# SR_Latch.net
KiCad netlist of a schematic drawn in Altium Designer
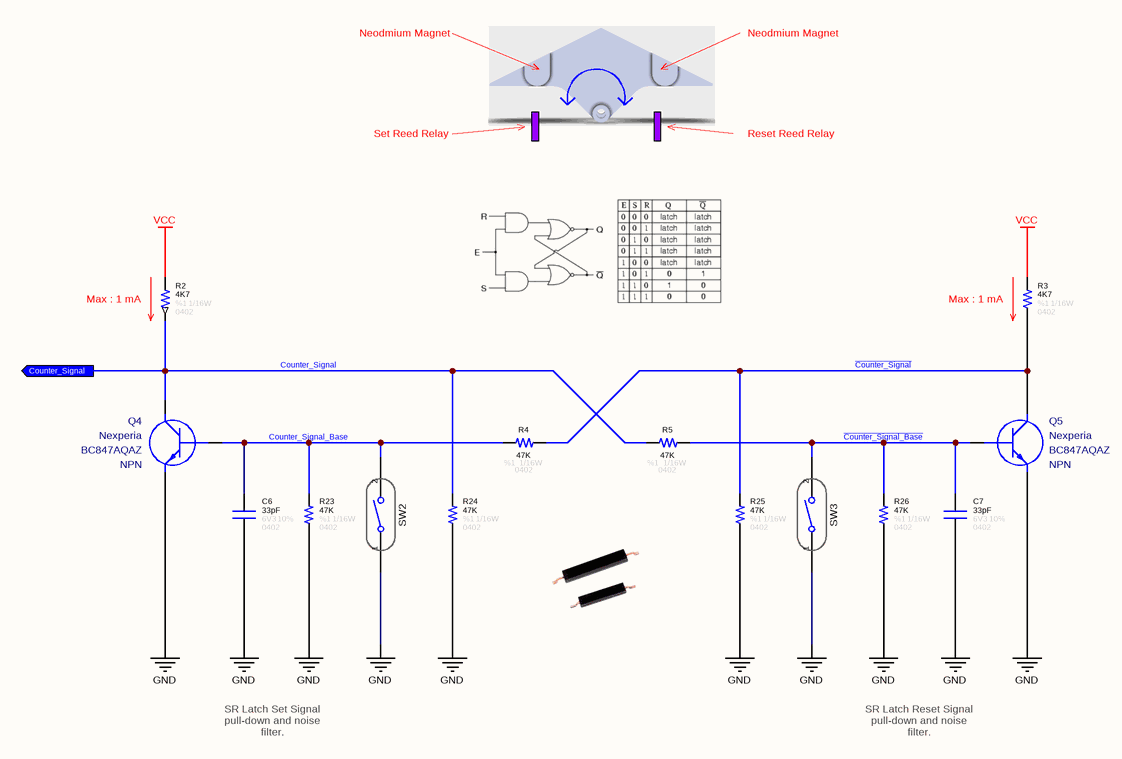
[diagram p0: SR Latch.SchDoc]

(export (version "E")
  (design (tool "Eeschema 10.0.6"))
  (components
    (comp (ref "C6")
      (value "33pF")
      (footprint "CAPACITOR_0402")
      (description "Capacitor - 33pF [0402] (Ceramic)")
      (fields
        (field (name "MANUFACTURER PART NUMBER") "C0402C330J9RACAUTO")
        (field (name "TOLERANCE") "10%")
        (field (name "CASE") "0402")
        (field (name "VOLTAGE") "6V3")
      )
      (libsource (lib "P101DA_Library") (part "Capacitor - 33pF [0402-6V3]"))
    )
    (comp (ref "C7")
      (value "33pF")
      (footprint "CAPACITOR_0402")
      (description "Capacitor - 33pF [0402] (Ceramic)")
      (fields
        (field (name "MANUFACTURER PART NUMBER") "C0402C330J9RACAUTO")
        (field (name "TOLERANCE") "10%")
        (field (name "CASE") "0402")
        (field (name "VOLTAGE") "6V3")
      )
      (libsource (lib "P101DA_Library") (part "Capacitor - 33pF [0402-6V3]"))
    )
    (comp (ref "Q4")
      (value "BC847AQAZ")
      (footprint "SOT1215")
      (description "Bipolar NPN Transistors")
      (fields
        (field (name "MANUFACTURER NAME") "Nexperia")
        (field (name "MANUFACTURER PART NUMBER") "BC847AQAZ")
        (field (name "POLARITY") "NPN")
      )
      (libsource (lib "P101DA_Library") (part "Transistor - BC847"))
    )
    (comp (ref "Q5")
      (value "BC847AQAZ")
      (footprint "SOT1215")
      (description "Bipolar NPN Transistors")
      (fields
        (field (name "MANUFACTURER NAME") "Nexperia")
        (field (name "MANUFACTURER PART NUMBER") "BC847AQAZ")
        (field (name "POLARITY") "NPN")
      )
      (libsource (lib "P101DA_Library") (part "Transistor - BC847"))
    )
    (comp (ref "R2")
      (value "4K7")
      (footprint "RESISTOR_0402")
      (description "Thick Film Resistors - SMD 1/16 W 4.7 KOhm 1%")
      (fields
        (field (name "MANUFACTURER PART NUMBER") "CRCW04024K70FKED")
        (field (name "TOLERANCE") "%1")
        (field (name "CASE") "0402")
        (field (name "POWER") "1/16W")
        (field (name "Comment") "4K7 - 0402 - %1 - 1/16W")
      )
      (libsource (lib "P101DA_Library") (part "Resistor - 4K7 [0402]"))
    )
    (comp (ref "R3")
      (value "4K7")
      (footprint "RESISTOR_0402")
      (description "Thick Film Resistors - SMD 1/16 W 4.7 KOhm 1%")
      (fields
        (field (name "MANUFACTURER PART NUMBER") "CRCW04024K70FKED")
        (field (name "TOLERANCE") "%1")
        (field (name "CASE") "0402")
        (field (name "POWER") "1/16W")
        (field (name "Comment") "4K7 - 0402 - %1 - 1/16W")
      )
      (libsource (lib "P101DA_Library") (part "Resistor - 4K7 [0402]"))
    )
    (comp (ref "R4")
      (value "47K")
      (footprint "RESISTOR_0402")
      (description "Thick Film Resistors - SMD 1/16 W 47 KOhm 1%")
      (fields
        (field (name "MANUFACTURER PART NUMBER") "CRCW040247K0FKED")
        (field (name "TOLERANCE") "%1")
        (field (name "CASE") "0402")
        (field (name "POWER") "1/16W")
        (field (name "Comment") "47K - 0402 - %1 - 1/16W")
      )
      (libsource (lib "P101DA_Library") (part "Resistor - 47K [0402]"))
    )
    (comp (ref "R5")
      (value "47K")
      (footprint "RESISTOR_0402")
      (description "Thick Film Resistors - SMD 1/16 W 47 KOhm 1%")
      (fields
        (field (name "MANUFACTURER PART NUMBER") "CRCW040247K0FKED")
        (field (name "TOLERANCE") "%1")
        (field (name "CASE") "0402")
        (field (name "POWER") "1/16W")
        (field (name "Comment") "47K - 0402 - %1 - 1/16W")
      )
      (libsource (lib "P101DA_Library") (part "Resistor - 47K [0402]"))
    )
    (comp (ref "R23")
      (value "47K")
      (footprint "RESISTOR_0402")
      (description "Thick Film Resistors - SMD 1/16 W 47 KOhm 1%")
      (fields
        (field (name "MANUFACTURER PART NUMBER") "CRCW040247K0FKED")
        (field (name "TOLERANCE") "%1")
        (field (name "CASE") "0402")
        (field (name "POWER") "1/16W")
        (field (name "Comment") "47K - 0402 - %1 - 1/16W")
      )
      (libsource (lib "P101DA_Library") (part "Resistor - 47K [0402]"))
    )
    (comp (ref "R24")
      (value "47K")
      (footprint "RESISTOR_0402")
      (description "Thick Film Resistors - SMD 1/16 W 47 KOhm 1%")
      (fields
        (field (name "MANUFACTURER PART NUMBER") "CRCW040247K0FKED")
        (field (name "TOLERANCE") "%1")
        (field (name "CASE") "0402")
        (field (name "POWER") "1/16W")
        (field (name "Comment") "47K - 0402 - %1 - 1/16W")
      )
      (libsource (lib "P101DA_Library") (part "Resistor - 47K [0402]"))
    )
    (comp (ref "R25")
      (value "47K")
      (footprint "RESISTOR_0402")
      (description "Thick Film Resistors - SMD 1/16 W 47 KOhm 1%")
      (fields
        (field (name "MANUFACTURER PART NUMBER") "CRCW040247K0FKED")
        (field (name "TOLERANCE") "%1")
        (field (name "CASE") "0402")
        (field (name "POWER") "1/16W")
        (field (name "Comment") "47K - 0402 - %1 - 1/16W")
      )
      (libsource (lib "P101DA_Library") (part "Resistor - 47K [0402]"))
    )
    (comp (ref "R26")
      (value "47K")
      (footprint "RESISTOR_0402")
      (description "Thick Film Resistors - SMD 1/16 W 47 KOhm 1%")
      (fields
        (field (name "MANUFACTURER PART NUMBER") "CRCW040247K0FKED")
        (field (name "TOLERANCE") "%1")
        (field (name "CASE") "0402")
        (field (name "POWER") "1/16W")
        (field (name "Comment") "47K - 0402 - %1 - 1/16W")
      )
      (libsource (lib "P101DA_Library") (part "Resistor - 47K [0402]"))
    )
    (comp (ref "SW2")
      (value "Reed Relay")
      (footprint "REED Relay")
      (description "Reed relay - SMD 11.7 mm")
      (fields (field (name "MANUFACTURER PART NUMBER") "MKA-10110MS"))
      (libsource (lib "P101DA_Library") (part "Switch - Reed Relay"))
    )
    (comp (ref "SW3")
      (value "Reed Relay")
      (footprint "REED Relay")
      (description "Reed relay - SMD 11.7 mm")
      (fields (field (name "MANUFACTURER PART NUMBER") "MKA-10110MS"))
      (libsource (lib "P101DA_Library") (part "Switch - Reed Relay"))
    )
  )
  (nets
    (net (code "1") (name "/Counter_Signal") (class "Default")
      (node (ref "Q4") (pin "3") (pinfunction "C_3") (pintype "passive"))
      (node (ref "R2") (pin "1") (pinfunction "1_1") (pintype "output"))
      (node (ref "R24") (pin "2") (pinfunction "2_2") (pintype "passive"))
      (node (ref "R5") (pin "2") (pinfunction "2_2") (pintype "passive"))
    )
    (net (code "2") (name "/Counter_Signal_Base") (class "Default")
      (node (ref "C6") (pin "2") (pinfunction "2_2") (pintype "passive"))
      (node (ref "Q4") (pin "1") (pinfunction "B_1") (pintype "passive"))
      (node (ref "R23") (pin "2") (pinfunction "2_2") (pintype "passive"))
      (node (ref "R4") (pin "2") (pinfunction "2_2") (pintype "passive"))
      (node (ref "SW2") (pin "2") (pinfunction "COM_2") (pintype "passive"))
    )
    (net (code "3") (name "/~{Counter_Signal_Base}") (class "Default")
      (node (ref "C7") (pin "2") (pinfunction "2_2") (pintype "passive"))
      (node (ref "Q5") (pin "1") (pinfunction "B_1") (pintype "passive"))
      (node (ref "R26") (pin "2") (pinfunction "2_2") (pintype "passive"))
      (node (ref "R5") (pin "1") (pinfunction "1_1") (pintype "passive"))
      (node (ref "SW3") (pin "2") (pinfunction "COM_2") (pintype "passive"))
    )
    (net (code "4") (name "/~{Counter_Signal}") (class "Default")
      (node (ref "Q5") (pin "3") (pinfunction "C_3") (pintype "passive"))
      (node (ref "R25") (pin "2") (pinfunction "2_2") (pintype "passive"))
      (node (ref "R3") (pin "1") (pinfunction "1_1") (pintype "output"))
      (node (ref "R4") (pin "1") (pinfunction "1_1") (pintype "passive"))
    )
    (net (code "5") (name "GND") (class "Default")
      (node (ref "C6") (pin "1") (pinfunction "1_1") (pintype "passive"))
      (node (ref "C7") (pin "1") (pinfunction "1_1") (pintype "passive"))
      (node (ref "Q4") (pin "2") (pinfunction "E_2") (pintype "passive"))
      (node (ref "Q5") (pin "2") (pinfunction "E_2") (pintype "passive"))
      (node (ref "R23") (pin "1") (pinfunction "1_1") (pintype "passive"))
      (node (ref "R24") (pin "1") (pinfunction "1_1") (pintype "passive"))
      (node (ref "R25") (pin "1") (pinfunction "1_1") (pintype "passive"))
      (node (ref "R26") (pin "1") (pinfunction "1_1") (pintype "passive"))
      (node (ref "SW2") (pin "1") (pinfunction "NC_1") (pintype "passive"))
      (node (ref "SW3") (pin "1") (pinfunction "NC_1") (pintype "passive"))
    )
    (net (code "6") (name "VCC") (class "Default")
      (node (ref "R2") (pin "2") (pinfunction "2_2") (pintype "passive"))
      (node (ref "R3") (pin "2") (pinfunction "2_2") (pintype "passive"))
    )
  )
)
